# untitled.net
KiCad netlist of a schematic drawn in EAGLE
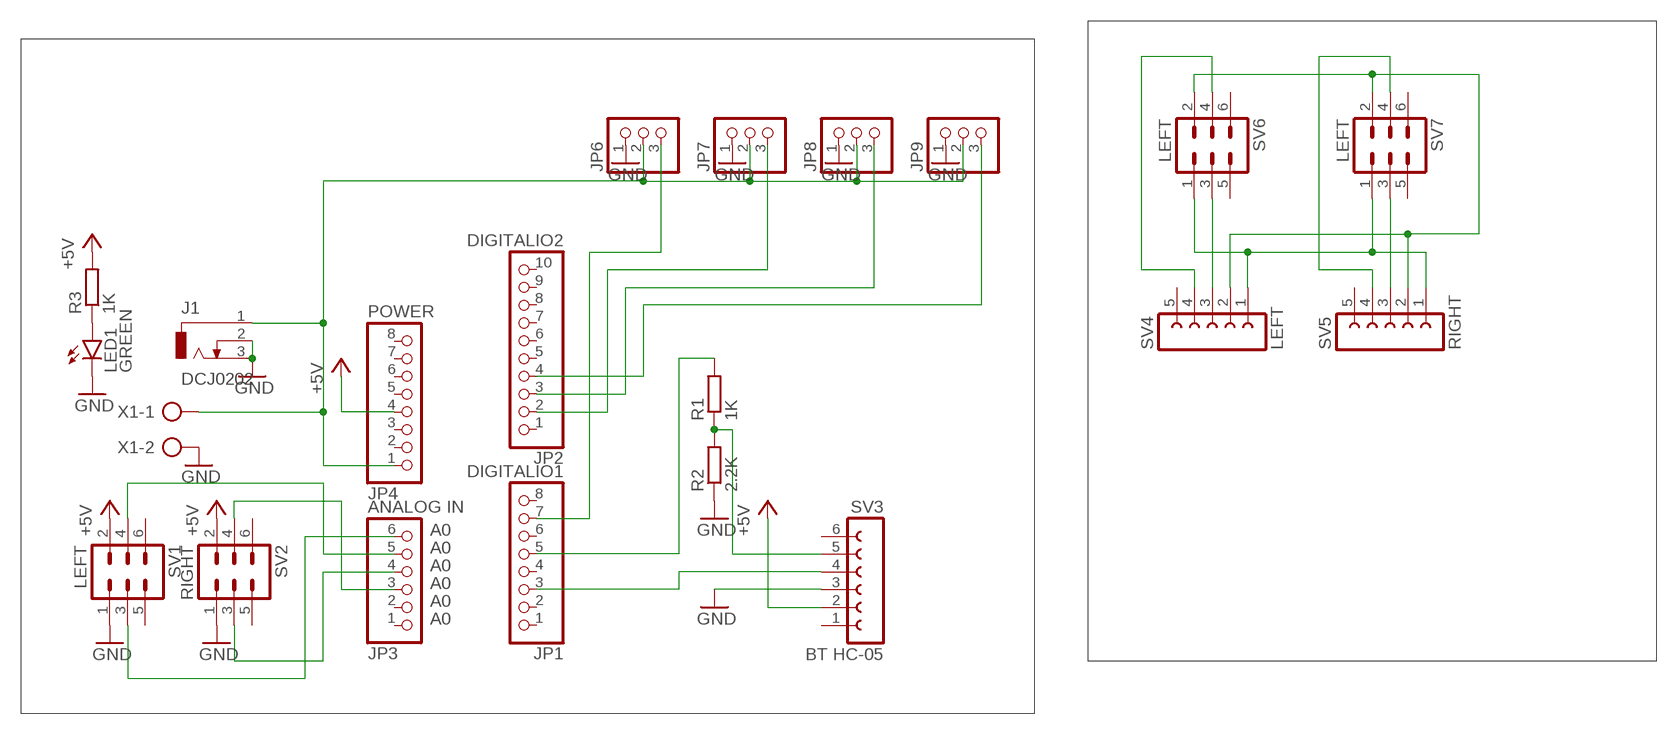
[diagram p0: schematic, sheet 1]

(export (version "E")
  (design (tool "Eeschema 10.0.6"))
  (components
    (comp (ref "J1")
      (value "DCJ0202")
      (footprint "eagle-import:DCJ0202")
      (libsource (lib "eagle-import") (part "DCJ0202"))
    )
    (comp (ref "JP1")
      (value "DIGITALIO1")
      (footprint "eagle-import:1X08")
      (libsource (lib "eagle-import") (part "PINHD-1X8"))
    )
    (comp (ref "JP2")
      (value "DIGITALIO2")
      (footprint "eagle-import:1X10")
      (libsource (lib "eagle-import") (part "PINHD-1X10"))
    )
    (comp (ref "JP3")
      (value "ANALOG IN")
      (footprint "eagle-import:1X06")
      (libsource (lib "eagle-import") (part "PINHD-1X6"))
    )
    (comp (ref "JP4")
      (value "POWER")
      (footprint "eagle-import:1X08")
      (libsource (lib "eagle-import") (part "PINHD-1X8"))
    )
    (comp (ref "JP6")
      (value "PINHD-1X3")
      (footprint "eagle-import:1X03")
      (libsource (lib "eagle-import") (part "PINHD-1X3"))
    )
    (comp (ref "JP7")
      (value "PINHD-1X3")
      (footprint "eagle-import:1X03")
      (libsource (lib "eagle-import") (part "PINHD-1X3"))
    )
    (comp (ref "JP8")
      (value "PINHD-1X3")
      (footprint "eagle-import:1X03")
      (libsource (lib "eagle-import") (part "PINHD-1X3"))
    )
    (comp (ref "JP9")
      (value "PINHD-1X3")
      (footprint "eagle-import:1X03")
      (libsource (lib "eagle-import") (part "PINHD-1X3"))
    )
    (comp (ref "LED1")
      (value "GREEN")
      (footprint "eagle-import:LED3MM")
      (libsource (lib "eagle-import") (part "LED3MM"))
    )
    (comp (ref "R1")
      (value "1K")
      (footprint "eagle-import:0207_10")
      (libsource (lib "eagle-import") (part "R-EU_0207/10"))
    )
    (comp (ref "R2")
      (value "2.2K")
      (footprint "eagle-import:0207_10")
      (libsource (lib "eagle-import") (part "R-EU_0207/10"))
    )
    (comp (ref "R3")
      (value "1K")
      (footprint "eagle-import:0207_10")
      (libsource (lib "eagle-import") (part "R-EU_0207/10"))
    )
    (comp (ref "SV1")
      (value "LEFT")
      (footprint "eagle-import:ML6")
      (libsource (lib "eagle-import") (part "ML6"))
    )
    (comp (ref "SV2")
      (value "RIGHT")
      (footprint "eagle-import:ML6")
      (libsource (lib "eagle-import") (part "ML6"))
    )
    (comp (ref "SV3")
      (value "BT HC-05")
      (footprint "eagle-import:FE06W")
      (libsource (lib "eagle-import") (part "FE06W"))
    )
    (comp (ref "SV4")
      (value "LEFT")
      (footprint "eagle-import:FE05W")
      (libsource (lib "eagle-import") (part "FE05W"))
    )
    (comp (ref "SV5")
      (value "RIGHT")
      (footprint "eagle-import:FE05W")
      (libsource (lib "eagle-import") (part "FE05W"))
    )
    (comp (ref "SV6")
      (value "LEFT")
      (footprint "eagle-import:ML6")
      (libsource (lib "eagle-import") (part "ML6"))
    )
    (comp (ref "SV7")
      (value "LEFT")
      (footprint "eagle-import:ML6")
      (libsource (lib "eagle-import") (part "ML6"))
    )
    (comp (ref "X1")
      (value "AK300/2")
      (footprint "eagle-import:AK300_2")
      (libsource (lib "eagle-import") (part "AK300/2"))
    )
  )
  (nets
    (net (code "1") (name "+5V") (class "Default")
      (node (ref "JP4") (pin "4") (pinfunction "4_4") (pintype "passive"))
      (node (ref "R3") (pin "2") (pinfunction "2_2") (pintype "passive"))
      (node (ref "SV1") (pin "2") (pinfunction "2_2") (pintype "passive"))
      (node (ref "SV2") (pin "2") (pinfunction "2_2") (pintype "passive"))
      (node (ref "SV3") (pin "2") (pinfunction "2_2") (pintype "passive"))
    )
    (net (code "2") (name "GND") (class "Default")
      (node (ref "J1") (pin "2") (pinfunction "2_2") (pintype "passive"))
      (node (ref "J1") (pin "3") (pinfunction "3_3") (pintype "passive"))
      (node (ref "JP6") (pin "1") (pinfunction "1_1") (pintype "passive"))
      (node (ref "JP7") (pin "1") (pinfunction "1_1") (pintype "passive"))
      (node (ref "JP8") (pin "1") (pinfunction "1_1") (pintype "passive"))
      (node (ref "JP9") (pin "1") (pinfunction "1_1") (pintype "passive"))
      (node (ref "LED1") (pin "K") (pinfunction "C_K") (pintype "passive"))
      (node (ref "R2") (pin "1") (pinfunction "1_1") (pintype "passive"))
      (node (ref "SV1") (pin "1") (pinfunction "1_1") (pintype "passive"))
      (node (ref "SV2") (pin "1") (pinfunction "1_1") (pintype "passive"))
      (node (ref "SV3") (pin "3") (pinfunction "3_3") (pintype "passive"))
      (node (ref "X1") (pin "2") (pinfunction "KL_2") (pintype "passive"))
    )
    (net (code "3") (name "Net-(JP1-Pad3)") (class "Default")
      (node (ref "JP1") (pin "3") (pinfunction "3_3") (pintype "passive"))
      (node (ref "SV3") (pin "4") (pinfunction "4_4") (pintype "passive"))
    )
    (net (code "4") (name "Net-(JP1-Pad5)") (class "Default")
      (node (ref "JP1") (pin "5") (pinfunction "5_5") (pintype "passive"))
      (node (ref "R1") (pin "2") (pinfunction "2_2") (pintype "passive"))
    )
    (net (code "5") (name "Net-(JP1-Pad7)") (class "Default")
      (node (ref "JP1") (pin "7") (pinfunction "7_7") (pintype "passive"))
      (node (ref "JP6") (pin "3") (pinfunction "3_3") (pintype "passive"))
    )
    (net (code "6") (name "Net-(JP2-Pad2)") (class "Default")
      (node (ref "JP2") (pin "2") (pinfunction "2_2") (pintype "passive"))
      (node (ref "JP7") (pin "3") (pinfunction "3_3") (pintype "passive"))
    )
    (net (code "7") (name "Net-(JP2-Pad3)") (class "Default")
      (node (ref "JP2") (pin "3") (pinfunction "3_3") (pintype "passive"))
      (node (ref "JP8") (pin "3") (pinfunction "3_3") (pintype "passive"))
    )
    (net (code "8") (name "Net-(JP2-Pad4)") (class "Default")
      (node (ref "JP2") (pin "4") (pinfunction "4_4") (pintype "passive"))
      (node (ref "JP9") (pin "3") (pinfunction "3_3") (pintype "passive"))
    )
    (net (code "9") (name "Net-(JP3-Pad3)") (class "Default")
      (node (ref "JP3") (pin "3") (pinfunction "3_3") (pintype "passive"))
      (node (ref "SV2") (pin "4") (pinfunction "4_4") (pintype "passive"))
    )
    (net (code "10") (name "Net-(JP3-Pad4)") (class "Default")
      (node (ref "JP3") (pin "4") (pinfunction "4_4") (pintype "passive"))
      (node (ref "SV2") (pin "3") (pinfunction "3_3") (pintype "passive"))
    )
    (net (code "11") (name "Net-(JP3-Pad5)") (class "Default")
      (node (ref "JP3") (pin "5") (pinfunction "5_5") (pintype "passive"))
      (node (ref "SV1") (pin "4") (pinfunction "4_4") (pintype "passive"))
    )
    (net (code "12") (name "Net-(JP3-Pad6)") (class "Default")
      (node (ref "JP3") (pin "6") (pinfunction "6_6") (pintype "passive"))
      (node (ref "SV1") (pin "3") (pinfunction "3_3") (pintype "passive"))
    )
    (net (code "13") (name "Net-(LED1-PadA)") (class "Default")
      (node (ref "LED1") (pin "A") (pinfunction "A_A") (pintype "passive"))
      (node (ref "R3") (pin "1") (pinfunction "1_1") (pintype "passive"))
    )
    (net (code "14") (name "Net-(R1-Pad1)") (class "Default")
      (node (ref "R1") (pin "1") (pinfunction "1_1") (pintype "passive"))
      (node (ref "R2") (pin "2") (pinfunction "2_2") (pintype "passive"))
      (node (ref "SV3") (pin "5") (pinfunction "5_5") (pintype "passive"))
    )
    (net (code "15") (name "Net-(SV4-Pad1)") (class "Default")
      (node (ref "SV4") (pin "1") (pinfunction "1_1") (pintype "passive"))
      (node (ref "SV5") (pin "1") (pinfunction "1_1") (pintype "passive"))
      (node (ref "SV6") (pin "1") (pinfunction "1_1") (pintype "passive"))
      (node (ref "SV7") (pin "1") (pinfunction "1_1") (pintype "passive"))
    )
    (net (code "16") (name "Net-(SV4-Pad2)") (class "Default")
      (node (ref "SV4") (pin "2") (pinfunction "2_2") (pintype "passive"))
      (node (ref "SV5") (pin "2") (pinfunction "2_2") (pintype "passive"))
      (node (ref "SV6") (pin "2") (pinfunction "2_2") (pintype "passive"))
      (node (ref "SV7") (pin "2") (pinfunction "2_2") (pintype "passive"))
    )
    (net (code "17") (name "Net-(SV4-Pad3)") (class "Default")
      (node (ref "SV4") (pin "3") (pinfunction "3_3") (pintype "passive"))
      (node (ref "SV6") (pin "3") (pinfunction "3_3") (pintype "passive"))
    )
    (net (code "18") (name "Net-(SV4-Pad4)") (class "Default")
      (node (ref "SV4") (pin "4") (pinfunction "4_4") (pintype "passive"))
      (node (ref "SV6") (pin "4") (pinfunction "4_4") (pintype "passive"))
    )
    (net (code "19") (name "Net-(SV5-Pad3)") (class "Default")
      (node (ref "SV5") (pin "3") (pinfunction "3_3") (pintype "passive"))
      (node (ref "SV7") (pin "3") (pinfunction "3_3") (pintype "passive"))
    )
    (net (code "20") (name "Net-(SV5-Pad4)") (class "Default")
      (node (ref "SV5") (pin "4") (pinfunction "4_4") (pintype "passive"))
      (node (ref "SV7") (pin "4") (pinfunction "4_4") (pintype "passive"))
    )
    (net (code "21") (name "Net-(X1A-KL)") (class "Default")
      (node (ref "J1") (pin "1") (pinfunction "1_1") (pintype "passive"))
      (node (ref "JP4") (pin "1") (pinfunction "1_1") (pintype "passive"))
      (node (ref "JP6") (pin "2") (pinfunction "2_2") (pintype "passive"))
      (node (ref "JP7") (pin "2") (pinfunction "2_2") (pintype "passive"))
      (node (ref "JP8") (pin "2") (pinfunction "2_2") (pintype "passive"))
      (node (ref "JP9") (pin "2") (pinfunction "2_2") (pintype "passive"))
      (node (ref "X1") (pin "1") (pinfunction "KL_1") (pintype "passive"))
    )
    (net (code "22") (name "unconnected-(JP1-Pad1)") (class "Default")
      (node (ref "JP1") (pin "1") (pinfunction "1_1") (pintype "passive"))
    )
    (net (code "23") (name "unconnected-(JP1-Pad2)") (class "Default")
      (node (ref "JP1") (pin "2") (pinfunction "2_2") (pintype "passive"))
    )
    (net (code "24") (name "unconnected-(JP1-Pad4)") (class "Default")
      (node (ref "JP1") (pin "4") (pinfunction "4_4") (pintype "passive"))
    )
    (net (code "25") (name "unconnected-(JP1-Pad6)") (class "Default")
      (node (ref "JP1") (pin "6") (pinfunction "6_6") (pintype "passive"))
    )
    (net (code "26") (name "unconnected-(JP1-Pad8)") (class "Default")
      (node (ref "JP1") (pin "8") (pinfunction "8_8") (pintype "passive"))
    )
    (net (code "27") (name "unconnected-(JP2-Pad1)") (class "Default")
      (node (ref "JP2") (pin "1") (pinfunction "1_1") (pintype "passive"))
    )
    (net (code "28") (name "unconnected-(JP2-Pad5)") (class "Default")
      (node (ref "JP2") (pin "5") (pinfunction "5_5") (pintype "passive"))
    )
    (net (code "29") (name "unconnected-(JP2-Pad6)") (class "Default")
      (node (ref "JP2") (pin "6") (pinfunction "6_6") (pintype "passive"))
    )
    (net (code "30") (name "unconnected-(JP2-Pad7)") (class "Default")
      (node (ref "JP2") (pin "7") (pinfunction "7_7") (pintype "passive"))
    )
    (net (code "31") (name "unconnected-(JP2-Pad8)") (class "Default")
      (node (ref "JP2") (pin "8") (pinfunction "8_8") (pintype "passive"))
    )
    (net (code "32") (name "unconnected-(JP2-Pad9)") (class "Default")
      (node (ref "JP2") (pin "9") (pinfunction "9_9") (pintype "passive"))
    )
    (net (code "33") (name "unconnected-(JP2-Pad10)") (class "Default")
      (node (ref "JP2") (pin "10") (pinfunction "10_10") (pintype "passive"))
    )
    (net (code "34") (name "unconnected-(JP3-Pad1)") (class "Default")
      (node (ref "JP3") (pin "1") (pinfunction "1_1") (pintype "passive"))
    )
    (net (code "35") (name "unconnected-(JP3-Pad2)") (class "Default")
      (node (ref "JP3") (pin "2") (pinfunction "2_2") (pintype "passive"))
    )
    (net (code "36") (name "unconnected-(JP4-Pad2)") (class "Default")
      (node (ref "JP4") (pin "2") (pinfunction "2_2") (pintype "passive"))
    )
    (net (code "37") (name "unconnected-(JP4-Pad3)") (class "Default")
      (node (ref "JP4") (pin "3") (pinfunction "3_3") (pintype "passive"))
    )
    (net (code "38") (name "unconnected-(JP4-Pad5)") (class "Default")
      (node (ref "JP4") (pin "5") (pinfunction "5_5") (pintype "passive"))
    )
    (net (code "39") (name "unconnected-(JP4-Pad6)") (class "Default")
      (node (ref "JP4") (pin "6") (pinfunction "6_6") (pintype "passive"))
    )
    (net (code "40") (name "unconnected-(JP4-Pad7)") (class "Default")
      (node (ref "JP4") (pin "7") (pinfunction "7_7") (pintype "passive"))
    )
    (net (code "41") (name "unconnected-(JP4-Pad8)") (class "Default")
      (node (ref "JP4") (pin "8") (pinfunction "8_8") (pintype "passive"))
    )
    (net (code "42") (name "unconnected-(SV1-Pad5)") (class "Default")
      (node (ref "SV1") (pin "5") (pinfunction "5_5") (pintype "passive"))
    )
    (net (code "43") (name "unconnected-(SV1-Pad6)") (class "Default")
      (node (ref "SV1") (pin "6") (pinfunction "6_6") (pintype "passive"))
    )
    (net (code "44") (name "unconnected-(SV2-Pad5)") (class "Default")
      (node (ref "SV2") (pin "5") (pinfunction "5_5") (pintype "passive"))
    )
    (net (code "45") (name "unconnected-(SV2-Pad6)") (class "Default")
      (node (ref "SV2") (pin "6") (pinfunction "6_6") (pintype "passive"))
    )
    (net (code "46") (name "unconnected-(SV3-Pad1)") (class "Default")
      (node (ref "SV3") (pin "1") (pinfunction "1_1") (pintype "passive"))
    )
    (net (code "47") (name "unconnected-(SV3-Pad6)") (class "Default")
      (node (ref "SV3") (pin "6") (pinfunction "6_6") (pintype "passive"))
    )
    (net (code "48") (name "unconnected-(SV4-Pad5)") (class "Default")
      (node (ref "SV4") (pin "5") (pinfunction "5_5") (pintype "passive"))
    )
    (net (code "49") (name "unconnected-(SV5-Pad5)") (class "Default")
      (node (ref "SV5") (pin "5") (pinfunction "5_5") (pintype "passive"))
    )
    (net (code "50") (name "unconnected-(SV6-Pad5)") (class "Default")
      (node (ref "SV6") (pin "5") (pinfunction "5_5") (pintype "passive"))
    )
    (net (code "51") (name "unconnected-(SV6-Pad6)") (class "Default")
      (node (ref "SV6") (pin "6") (pinfunction "6_6") (pintype "passive"))
    )
    (net (code "52") (name "unconnected-(SV7-Pad5)") (class "Default")
      (node (ref "SV7") (pin "5") (pinfunction "5_5") (pintype "passive"))
    )
    (net (code "53") (name "unconnected-(SV7-Pad6)") (class "Default")
      (node (ref "SV7") (pin "6") (pinfunction "6_6") (pintype "passive"))
    )
  )
)
